# decoupling.net
KiCad netlist of a schematic drawn in Altium Designer
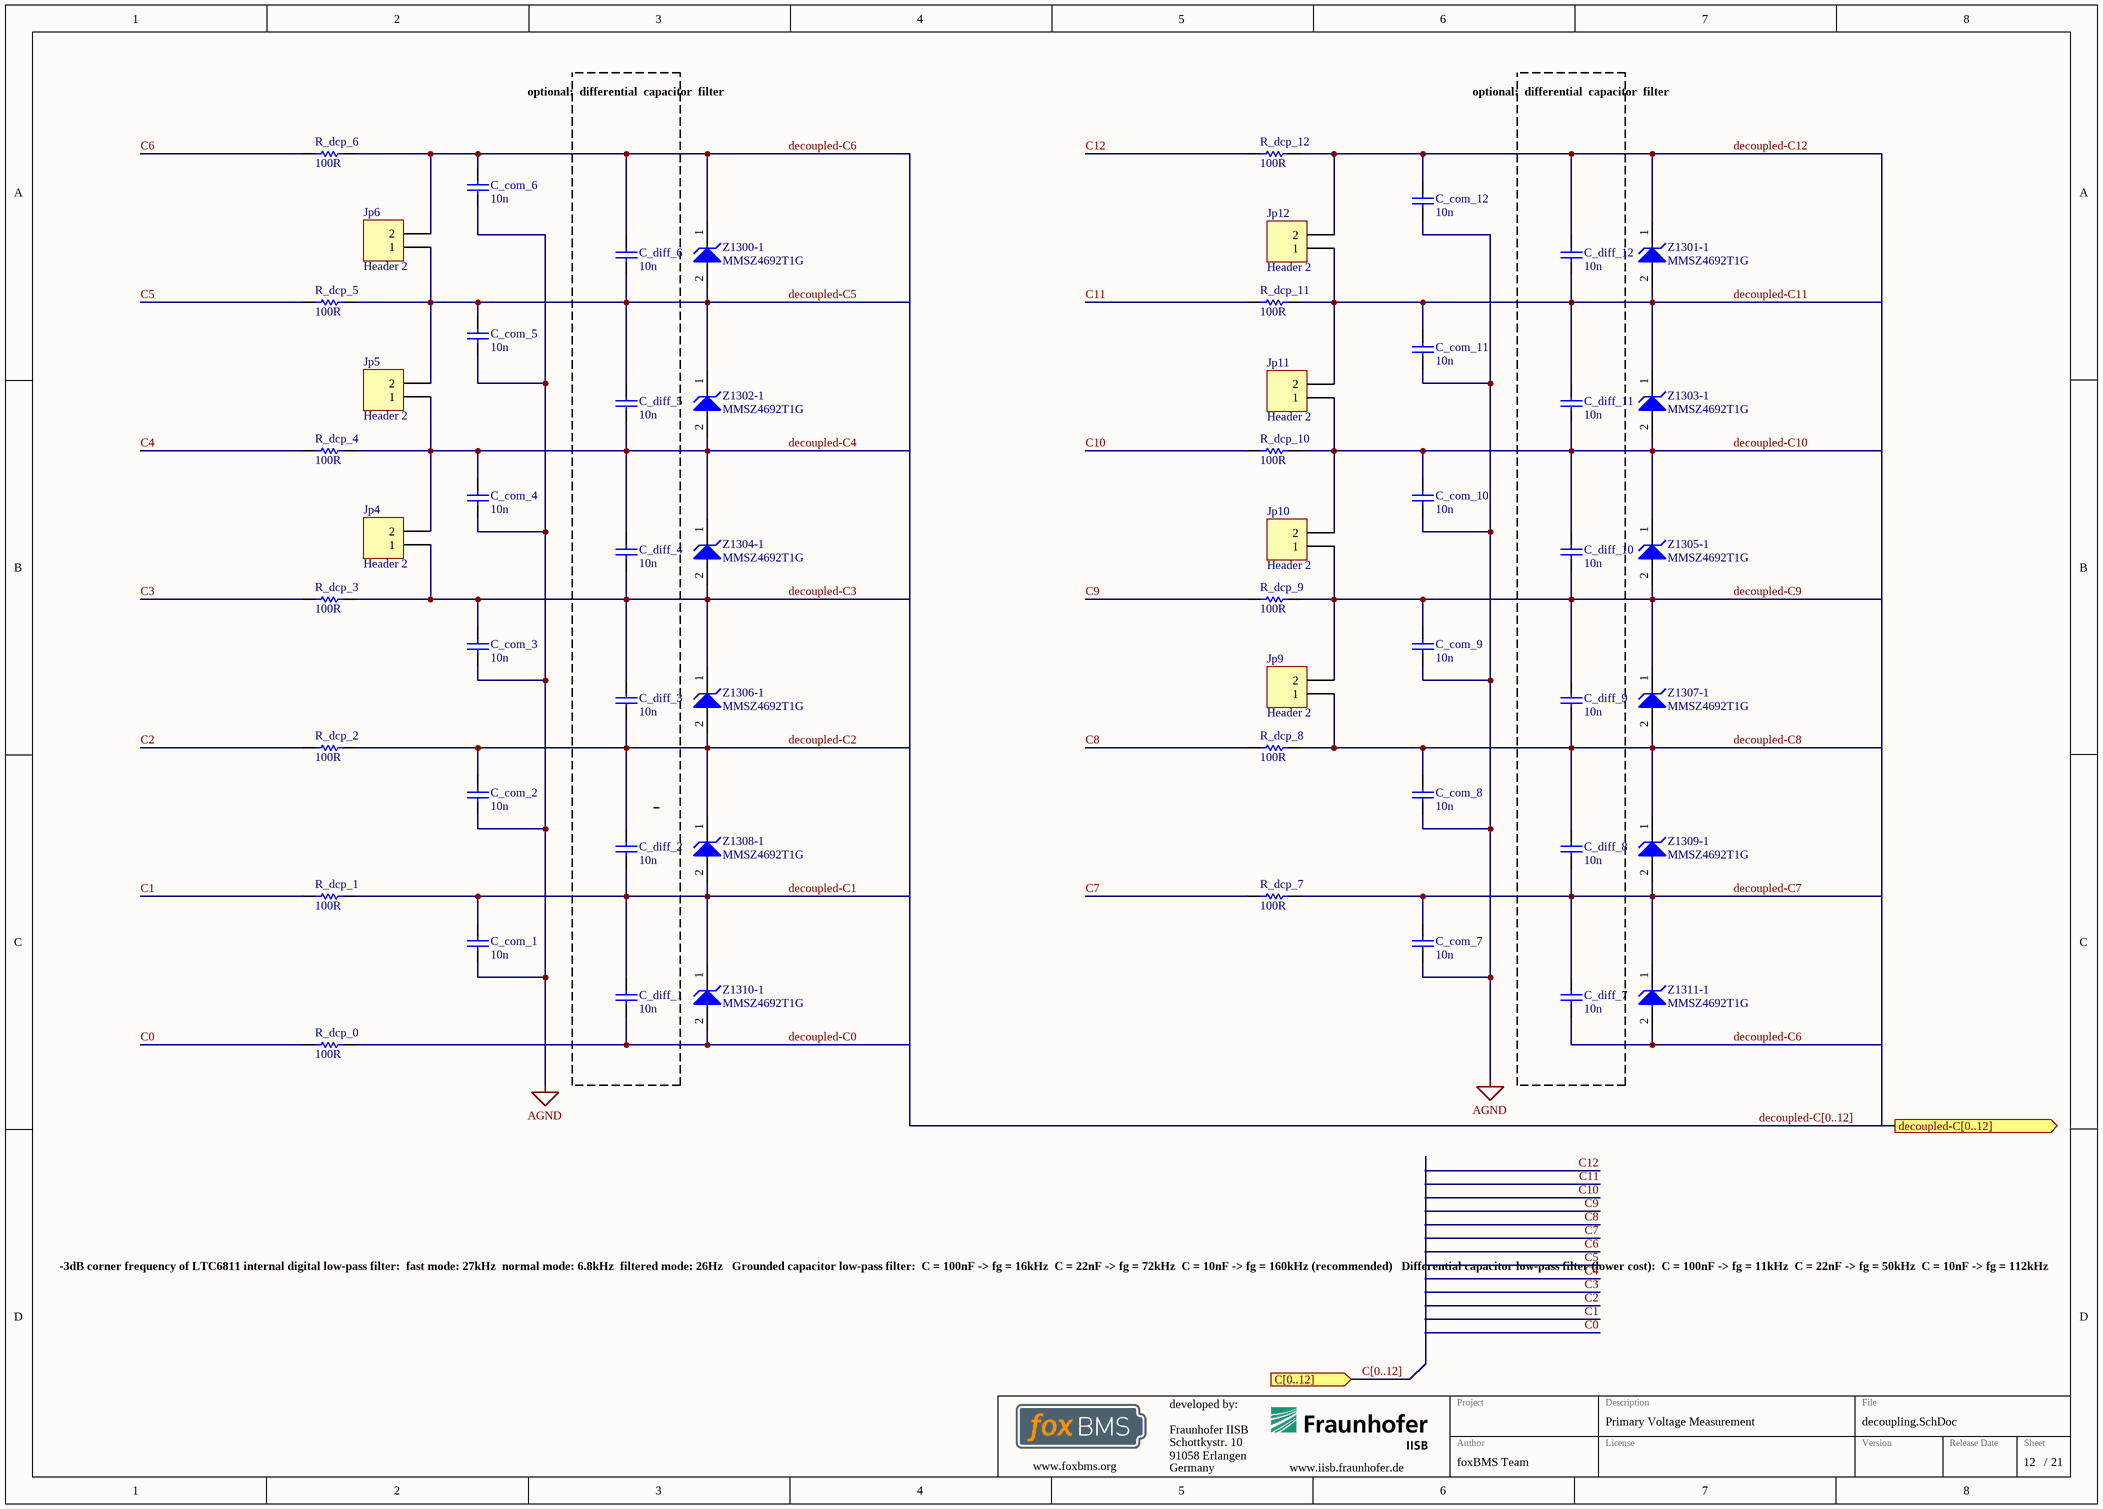
[diagram p0: decoupling.SchDoc]

(export (version "E")
  (design (tool "Eeschema 10.0.6"))
  (components
    (comp (ref "C_com_1")
      (value "10n")
      (footprint "CAPC0603(1608)55_N")
      (description "Keramikvielschichtkondensator, SMD, Baureihe MC, ± 10%")
      (fields (field (name "MANUFACTURER") "TDK") (field (name "TOLERANCE") "± 10%"))
      (libsource (lib "Res&Caps") (part "Cap 10n"))
    )
    (comp (ref "C_com_2")
      (value "10n")
      (footprint "CAPC0603(1608)55_N")
      (description "Keramikvielschichtkondensator, SMD, Baureihe MC, ± 10%")
      (fields (field (name "MANUFACTURER") "TDK") (field (name "TOLERANCE") "± 10%"))
      (libsource (lib "Res&Caps") (part "Cap 10n"))
    )
    (comp (ref "C_com_3")
      (value "10n")
      (footprint "CAPC0603(1608)55_N")
      (description "Keramikvielschichtkondensator, SMD, Baureihe MC, ± 10%")
      (fields (field (name "MANUFACTURER") "TDK") (field (name "TOLERANCE") "± 10%"))
      (libsource (lib "Res&Caps") (part "Cap 10n"))
    )
    (comp (ref "C_com_4")
      (value "10n")
      (footprint "CAPC0603(1608)55_N")
      (description "Keramikvielschichtkondensator, SMD, Baureihe MC, ± 10%")
      (fields (field (name "MANUFACTURER") "TDK") (field (name "TOLERANCE") "± 10%"))
      (libsource (lib "Res&Caps") (part "Cap 10n"))
    )
    (comp (ref "C_com_5")
      (value "10n")
      (footprint "CAPC0603(1608)55_N")
      (description "Keramikvielschichtkondensator, SMD, Baureihe MC, ± 10%")
      (fields (field (name "MANUFACTURER") "TDK") (field (name "TOLERANCE") "± 10%"))
      (libsource (lib "Res&Caps") (part "Cap 10n"))
    )
    (comp (ref "C_com_6")
      (value "10n")
      (footprint "CAPC0603(1608)55_N")
      (description "Keramikvielschichtkondensator, SMD, Baureihe MC, ± 10%")
      (fields (field (name "MANUFACTURER") "TDK") (field (name "TOLERANCE") "± 10%"))
      (libsource (lib "Res&Caps") (part "Cap 10n"))
    )
    (comp (ref "C_com_7")
      (value "10n")
      (footprint "CAPC0603(1608)55_N")
      (description "Keramikvielschichtkondensator, SMD, Baureihe MC, ± 10%")
      (fields (field (name "MANUFACTURER") "TDK") (field (name "TOLERANCE") "± 10%"))
      (libsource (lib "Res&Caps") (part "Cap 10n"))
    )
    (comp (ref "C_com_8")
      (value "10n")
      (footprint "CAPC0603(1608)55_N")
      (description "Keramikvielschichtkondensator, SMD, Baureihe MC, ± 10%")
      (fields (field (name "MANUFACTURER") "TDK") (field (name "TOLERANCE") "± 10%"))
      (libsource (lib "Res&Caps") (part "Cap 10n"))
    )
    (comp (ref "C_com_9")
      (value "10n")
      (footprint "CAPC0603(1608)55_N")
      (description "Keramikvielschichtkondensator, SMD, Baureihe MC, ± 10%")
      (fields (field (name "MANUFACTURER") "TDK") (field (name "TOLERANCE") "± 10%"))
      (libsource (lib "Res&Caps") (part "Cap 10n"))
    )
    (comp (ref "C_com_10")
      (value "10n")
      (footprint "CAPC0603(1608)55_N")
      (description "Keramikvielschichtkondensator, SMD, Baureihe MC, ± 10%")
      (fields (field (name "MANUFACTURER") "TDK") (field (name "TOLERANCE") "± 10%"))
      (libsource (lib "Res&Caps") (part "Cap 10n"))
    )
    (comp (ref "C_com_11")
      (value "10n")
      (footprint "CAPC0603(1608)55_N")
      (description "Keramikvielschichtkondensator, SMD, Baureihe MC, ± 10%")
      (fields (field (name "MANUFACTURER") "TDK") (field (name "TOLERANCE") "± 10%"))
      (libsource (lib "Res&Caps") (part "Cap 10n"))
    )
    (comp (ref "C_com_12")
      (value "10n")
      (footprint "CAPC0603(1608)55_N")
      (description "Keramikvielschichtkondensator, SMD, Baureihe MC, ± 10%")
      (fields (field (name "MANUFACTURER") "TDK") (field (name "TOLERANCE") "± 10%"))
      (libsource (lib "Res&Caps") (part "Cap 10n"))
    )
    (comp (ref "C_diff_1")
      (value "10n")
      (footprint "CAPC0603(1608)55_N")
      (description "Keramikvielschichtkondensator, SMD, Baureihe MC, ± 10%")
      (fields (field (name "MANUFACTURER") "TDK") (field (name "TOLERANCE") "± 10%"))
      (libsource (lib "Res&Caps") (part "Cap 10n"))
    )
    (comp (ref "C_diff_2")
      (value "10n")
      (footprint "CAPC0603(1608)55_N")
      (description "Keramikvielschichtkondensator, SMD, Baureihe MC, ± 10%")
      (fields (field (name "MANUFACTURER") "TDK") (field (name "TOLERANCE") "± 10%"))
      (libsource (lib "Res&Caps") (part "Cap 10n"))
    )
    (comp (ref "C_diff_3")
      (value "10n")
      (footprint "CAPC0603(1608)55_N")
      (description "Keramikvielschichtkondensator, SMD, Baureihe MC, ± 10%")
      (fields (field (name "MANUFACTURER") "TDK") (field (name "TOLERANCE") "± 10%"))
      (libsource (lib "Res&Caps") (part "Cap 10n"))
    )
    (comp (ref "C_diff_4")
      (value "10n")
      (footprint "CAPC0603(1608)55_N")
      (description "Keramikvielschichtkondensator, SMD, Baureihe MC, ± 10%")
      (fields (field (name "MANUFACTURER") "TDK") (field (name "TOLERANCE") "± 10%"))
      (libsource (lib "Res&Caps") (part "Cap 10n"))
    )
    (comp (ref "C_diff_5")
      (value "10n")
      (footprint "CAPC0603(1608)55_N")
      (description "Keramikvielschichtkondensator, SMD, Baureihe MC, ± 10%")
      (fields (field (name "MANUFACTURER") "TDK") (field (name "TOLERANCE") "± 10%"))
      (libsource (lib "Res&Caps") (part "Cap 10n"))
    )
    (comp (ref "C_diff_6")
      (value "10n")
      (footprint "CAPC0603(1608)55_N")
      (description "Keramikvielschichtkondensator, SMD, Baureihe MC, ± 10%")
      (fields (field (name "MANUFACTURER") "TDK") (field (name "TOLERANCE") "± 10%"))
      (libsource (lib "Res&Caps") (part "Cap 10n"))
    )
    (comp (ref "C_diff_7")
      (value "10n")
      (footprint "CAPC0603(1608)55_N")
      (description "Keramikvielschichtkondensator, SMD, Baureihe MC, ± 10%")
      (fields (field (name "MANUFACTURER") "TDK") (field (name "TOLERANCE") "± 10%"))
      (libsource (lib "Res&Caps") (part "Cap 10n"))
    )
    (comp (ref "C_diff_8")
      (value "10n")
      (footprint "CAPC0603(1608)55_N")
      (description "Keramikvielschichtkondensator, SMD, Baureihe MC, ± 10%")
      (fields (field (name "MANUFACTURER") "TDK") (field (name "TOLERANCE") "± 10%"))
      (libsource (lib "Res&Caps") (part "Cap 10n"))
    )
    (comp (ref "C_diff_9")
      (value "10n")
      (footprint "CAPC0603(1608)55_N")
      (description "Keramikvielschichtkondensator, SMD, Baureihe MC, ± 10%")
      (fields (field (name "MANUFACTURER") "TDK") (field (name "TOLERANCE") "± 10%"))
      (libsource (lib "Res&Caps") (part "Cap 10n"))
    )
    (comp (ref "C_diff_10")
      (value "10n")
      (footprint "CAPC0603(1608)55_N")
      (description "Keramikvielschichtkondensator, SMD, Baureihe MC, ± 10%")
      (fields (field (name "MANUFACTURER") "TDK") (field (name "TOLERANCE") "± 10%"))
      (libsource (lib "Res&Caps") (part "Cap 10n"))
    )
    (comp (ref "C_diff_11")
      (value "10n")
      (footprint "CAPC0603(1608)55_N")
      (description "Keramikvielschichtkondensator, SMD, Baureihe MC, ± 10%")
      (fields (field (name "MANUFACTURER") "TDK") (field (name "TOLERANCE") "± 10%"))
      (libsource (lib "Res&Caps") (part "Cap 10n"))
    )
    (comp (ref "C_diff_12")
      (value "10n")
      (footprint "CAPC0603(1608)55_N")
      (description "Keramikvielschichtkondensator, SMD, Baureihe MC, ± 10%")
      (fields (field (name "MANUFACTURER") "TDK") (field (name "TOLERANCE") "± 10%"))
      (libsource (lib "Res&Caps") (part "Cap 10n"))
    )
    (comp (ref "Jp4")
      (value "Header 2")
      (footprint "HDR1X2")
      (description "Header, 2-Pin")
      (fields (field (name "PUBLISHER") "Altium Limited"))
      (libsource (lib "Miscellaneous Connectors") (part "Header 2"))
    )
    (comp (ref "Jp5")
      (value "Header 2")
      (footprint "HDR1X2")
      (description "Header, 2-Pin")
      (fields (field (name "PUBLISHER") "Altium Limited"))
      (libsource (lib "Miscellaneous Connectors") (part "Header 2"))
    )
    (comp (ref "Jp6")
      (value "Header 2")
      (footprint "HDR1X2")
      (description "Header, 2-Pin")
      (fields (field (name "PUBLISHER") "Altium Limited"))
      (libsource (lib "Miscellaneous Connectors") (part "Header 2"))
    )
    (comp (ref "Jp9")
      (value "Header 2")
      (footprint "HDR1X2")
      (description "Header, 2-Pin")
      (fields (field (name "PUBLISHER") "Altium Limited"))
      (libsource (lib "Miscellaneous Connectors") (part "Header 2"))
    )
    (comp (ref "Jp10")
      (value "Header 2")
      (footprint "HDR1X2")
      (description "Header, 2-Pin")
      (fields (field (name "PUBLISHER") "Altium Limited"))
      (libsource (lib "Miscellaneous Connectors") (part "Header 2"))
    )
    (comp (ref "Jp11")
      (value "Header 2")
      (footprint "HDR1X2")
      (description "Header, 2-Pin")
      (fields (field (name "PUBLISHER") "Altium Limited"))
      (libsource (lib "Miscellaneous Connectors") (part "Header 2"))
    )
    (comp (ref "Jp12")
      (value "Header 2")
      (footprint "HDR1X2")
      (description "Header, 2-Pin")
      (fields (field (name "PUBLISHER") "Altium Limited"))
      (libsource (lib "Miscellaneous Connectors") (part "Header 2"))
    )
    (comp (ref "R_dcp_0")
      (value "100R")
      (footprint "RESC0603(1608)_N")
      (description "Chipwiderstand, SMD, Baureihe MC, 1%")
      (fields (field (name "MANUFACTURER") "Multicomp") (field (name "POWER") "100mW"))
      (libsource (lib "Res&Caps") (part "Res 100R"))
    )
    (comp (ref "R_dcp_1")
      (value "100R")
      (footprint "RESC0603(1608)_N")
      (description "Chipwiderstand, SMD, Baureihe MC, 1%")
      (fields (field (name "MANUFACTURER") "Multicomp") (field (name "POWER") "100mW"))
      (libsource (lib "Res&Caps") (part "Res 100R"))
    )
    (comp (ref "R_dcp_2")
      (value "100R")
      (footprint "RESC0603(1608)_N")
      (description "Chipwiderstand, SMD, Baureihe MC, 1%")
      (fields (field (name "MANUFACTURER") "Multicomp") (field (name "POWER") "100mW"))
      (libsource (lib "Res&Caps") (part "Res 100R"))
    )
    (comp (ref "R_dcp_3")
      (value "100R")
      (footprint "RESC0603(1608)_N")
      (description "Chipwiderstand, SMD, Baureihe MC, 1%")
      (fields (field (name "MANUFACTURER") "Multicomp") (field (name "POWER") "100mW"))
      (libsource (lib "Res&Caps") (part "Res 100R"))
    )
    (comp (ref "R_dcp_4")
      (value "100R")
      (footprint "RESC0603(1608)_N")
      (description "Chipwiderstand, SMD, Baureihe MC, 1%")
      (fields (field (name "MANUFACTURER") "Multicomp") (field (name "POWER") "100mW"))
      (libsource (lib "Res&Caps") (part "Res 100R"))
    )
    (comp (ref "R_dcp_5")
      (value "100R")
      (footprint "RESC0603(1608)_N")
      (description "Chipwiderstand, SMD, Baureihe MC, 1%")
      (fields (field (name "MANUFACTURER") "Multicomp") (field (name "POWER") "100mW"))
      (libsource (lib "Res&Caps") (part "Res 100R"))
    )
    (comp (ref "R_dcp_6")
      (value "100R")
      (footprint "RESC0603(1608)_N")
      (description "Chipwiderstand, SMD, Baureihe MC, 1%")
      (fields (field (name "MANUFACTURER") "Multicomp") (field (name "POWER") "100mW"))
      (libsource (lib "Res&Caps") (part "Res 100R"))
    )
    (comp (ref "R_dcp_7")
      (value "100R")
      (footprint "RESC0603(1608)_N")
      (description "Chipwiderstand, SMD, Baureihe MC, 1%")
      (fields (field (name "MANUFACTURER") "Multicomp") (field (name "POWER") "100mW"))
      (libsource (lib "Res&Caps") (part "Res 100R"))
    )
    (comp (ref "R_dcp_8")
      (value "100R")
      (footprint "RESC0603(1608)_N")
      (description "Chipwiderstand, SMD, Baureihe MC, 1%")
      (fields (field (name "MANUFACTURER") "Multicomp") (field (name "POWER") "100mW"))
      (libsource (lib "Res&Caps") (part "Res 100R"))
    )
    (comp (ref "R_dcp_9")
      (value "100R")
      (footprint "RESC0603(1608)_N")
      (description "Chipwiderstand, SMD, Baureihe MC, 1%")
      (fields (field (name "MANUFACTURER") "Multicomp") (field (name "POWER") "100mW"))
      (libsource (lib "Res&Caps") (part "Res 100R"))
    )
    (comp (ref "R_dcp_10")
      (value "100R")
      (footprint "RESC0603(1608)_N")
      (description "Chipwiderstand, SMD, Baureihe MC, 1%")
      (fields (field (name "MANUFACTURER") "Multicomp") (field (name "POWER") "100mW"))
      (libsource (lib "Res&Caps") (part "Res 100R"))
    )
    (comp (ref "R_dcp_11")
      (value "100R")
      (footprint "RESC0603(1608)_N")
      (description "Chipwiderstand, SMD, Baureihe MC, 1%")
      (fields (field (name "MANUFACTURER") "Multicomp") (field (name "POWER") "100mW"))
      (libsource (lib "Res&Caps") (part "Res 100R"))
    )
    (comp (ref "R_dcp_12")
      (value "100R")
      (footprint "RESC0603(1608)_N")
      (description "Chipwiderstand, SMD, Baureihe MC, 1%")
      (fields (field (name "MANUFACTURER") "Multicomp") (field (name "POWER") "100mW"))
      (libsource (lib "Res&Caps") (part "Res 100R"))
    )
    (comp (ref "Z1300-1")
      (value "MMSZ4692T1G")
      (footprint "ONSC-SOD-123-2-425-04_V")
      (description "Zener Voltage Regulator, 500 mW, 2-Pin SOD-123, Pb-Free, Tape and Reel")
      (fields (field (name "MANUFACTURER") "On Semiconductor"))
      (libsource (lib "Altium Content Vault") (part "ONSC-K1A2-2"))
    )
    (comp (ref "Z1301-1")
      (value "MMSZ4692T1G")
      (footprint "ONSC-SOD-123-2-425-04_V")
      (description "Zener Voltage Regulator, 500 mW, 2-Pin SOD-123, Pb-Free, Tape and Reel")
      (fields (field (name "MANUFACTURER") "On Semiconductor"))
      (libsource (lib "Altium Content Vault") (part "ONSC-K1A2-2"))
    )
    (comp (ref "Z1302-1")
      (value "MMSZ4692T1G")
      (footprint "ONSC-SOD-123-2-425-04_V")
      (description "Zener Voltage Regulator, 500 mW, 2-Pin SOD-123, Pb-Free, Tape and Reel")
      (fields (field (name "MANUFACTURER") "On Semiconductor"))
      (libsource (lib "Altium Content Vault") (part "ONSC-K1A2-2"))
    )
    (comp (ref "Z1303-1")
      (value "MMSZ4692T1G")
      (footprint "ONSC-SOD-123-2-425-04_V")
      (description "Zener Voltage Regulator, 500 mW, 2-Pin SOD-123, Pb-Free, Tape and Reel")
      (fields (field (name "MANUFACTURER") "On Semiconductor"))
      (libsource (lib "Altium Content Vault") (part "ONSC-K1A2-2"))
    )
    (comp (ref "Z1304-1")
      (value "MMSZ4692T1G")
      (footprint "ONSC-SOD-123-2-425-04_V")
      (description "Zener Voltage Regulator, 500 mW, 2-Pin SOD-123, Pb-Free, Tape and Reel")
      (fields (field (name "MANUFACTURER") "On Semiconductor"))
      (libsource (lib "Altium Content Vault") (part "ONSC-K1A2-2"))
    )
    (comp (ref "Z1305-1")
      (value "MMSZ4692T1G")
      (footprint "ONSC-SOD-123-2-425-04_V")
      (description "Zener Voltage Regulator, 500 mW, 2-Pin SOD-123, Pb-Free, Tape and Reel")
      (fields (field (name "MANUFACTURER") "On Semiconductor"))
      (libsource (lib "Altium Content Vault") (part "ONSC-K1A2-2"))
    )
    (comp (ref "Z1306-1")
      (value "MMSZ4692T1G")
      (footprint "ONSC-SOD-123-2-425-04_V")
      (description "Zener Voltage Regulator, 500 mW, 2-Pin SOD-123, Pb-Free, Tape and Reel")
      (fields (field (name "MANUFACTURER") "On Semiconductor"))
      (libsource (lib "Altium Content Vault") (part "ONSC-K1A2-2"))
    )
    (comp (ref "Z1307-1")
      (value "MMSZ4692T1G")
      (footprint "ONSC-SOD-123-2-425-04_V")
      (description "Zener Voltage Regulator, 500 mW, 2-Pin SOD-123, Pb-Free, Tape and Reel")
      (fields (field (name "MANUFACTURER") "On Semiconductor"))
      (libsource (lib "Altium Content Vault") (part "ONSC-K1A2-2"))
    )
    (comp (ref "Z1308-1")
      (value "MMSZ4692T1G")
      (footprint "ONSC-SOD-123-2-425-04_V")
      (description "Zener Voltage Regulator, 500 mW, 2-Pin SOD-123, Pb-Free, Tape and Reel")
      (fields (field (name "MANUFACTURER") "On Semiconductor"))
      (libsource (lib "Altium Content Vault") (part "ONSC-K1A2-2"))
    )
    (comp (ref "Z1309-1")
      (value "MMSZ4692T1G")
      (footprint "ONSC-SOD-123-2-425-04_V")
      (description "Zener Voltage Regulator, 500 mW, 2-Pin SOD-123, Pb-Free, Tape and Reel")
      (fields (field (name "MANUFACTURER") "On Semiconductor"))
      (libsource (lib "Altium Content Vault") (part "ONSC-K1A2-2"))
    )
    (comp (ref "Z1310-1")
      (value "MMSZ4692T1G")
      (footprint "ONSC-SOD-123-2-425-04_V")
      (description "Zener Voltage Regulator, 500 mW, 2-Pin SOD-123, Pb-Free, Tape and Reel")
      (fields (field (name "MANUFACTURER") "On Semiconductor"))
      (libsource (lib "Altium Content Vault") (part "ONSC-K1A2-2"))
    )
    (comp (ref "Z1311-1")
      (value "MMSZ4692T1G")
      (footprint "ONSC-SOD-123-2-425-04_V")
      (description "Zener Voltage Regulator, 500 mW, 2-Pin SOD-123, Pb-Free, Tape and Reel")
      (fields (field (name "MANUFACTURER") "On Semiconductor"))
      (libsource (lib "Altium Content Vault") (part "ONSC-K1A2-2"))
    )
  )
  (nets
    (net (code "1") (name "/C0") (class "Default")
      (node (ref "R_dcp_0") (pin "1") (pinfunction "1_1") (pintype "passive"))
    )
    (net (code "2") (name "/C1") (class "Default")
      (node (ref "R_dcp_1") (pin "1") (pinfunction "1_1") (pintype "passive"))
    )
    (net (code "3") (name "/C2") (class "Default")
      (node (ref "R_dcp_2") (pin "1") (pinfunction "1_1") (pintype "passive"))
    )
    (net (code "4") (name "/C3") (class "Default")
      (node (ref "R_dcp_3") (pin "1") (pinfunction "1_1") (pintype "passive"))
    )
    (net (code "5") (name "/C4") (class "Default")
      (node (ref "R_dcp_4") (pin "1") (pinfunction "1_1") (pintype "passive"))
    )
    (net (code "6") (name "/C5") (class "Default")
      (node (ref "R_dcp_5") (pin "1") (pinfunction "1_1") (pintype "passive"))
    )
    (net (code "7") (name "/C6") (class "Default")
      (node (ref "R_dcp_6") (pin "1") (pinfunction "1_1") (pintype "passive"))
    )
    (net (code "8") (name "/C7") (class "Default")
      (node (ref "R_dcp_7") (pin "1") (pinfunction "1_1") (pintype "passive"))
    )
    (net (code "9") (name "/C8") (class "Default")
      (node (ref "R_dcp_8") (pin "1") (pinfunction "1_1") (pintype "passive"))
    )
    (net (code "10") (name "/C9") (class "Default")
      (node (ref "R_dcp_9") (pin "1") (pinfunction "1_1") (pintype "passive"))
    )
    (net (code "11") (name "/C10") (class "Default")
      (node (ref "R_dcp_10") (pin "1") (pinfunction "1_1") (pintype "passive"))
    )
    (net (code "12") (name "/C11") (class "Default")
      (node (ref "R_dcp_11") (pin "1") (pinfunction "1_1") (pintype "passive"))
    )
    (net (code "13") (name "/C12") (class "Default")
      (node (ref "R_dcp_12") (pin "1") (pinfunction "1_1") (pintype "passive"))
    )
    (net (code "15") (name "/decoupled-C0") (class "Default")
      (node (ref "C_diff_1") (pin "1") (pinfunction "1_1") (pintype "passive"))
      (node (ref "R_dcp_0") (pin "2") (pinfunction "2_2") (pintype "passive"))
      (node (ref "Z1310-1") (pin "2") (pinfunction "A_2") (pintype "passive"))
    )
    (net (code "16") (name "/decoupled-C1") (class "Default")
      (node (ref "C_com_1") (pin "2") (pinfunction "2_2") (pintype "passive"))
      (node (ref "C_diff_1") (pin "2") (pinfunction "2_2") (pintype "passive"))
      (node (ref "C_diff_2") (pin "1") (pinfunction "1_1") (pintype "passive"))
      (node (ref "R_dcp_1") (pin "2") (pinfunction "2_2") (pintype "passive"))
      (node (ref "Z1308-1") (pin "2") (pinfunction "A_2") (pintype "passive"))
      (node (ref "Z1310-1") (pin "1") (pinfunction "K_1") (pintype "passive"))
    )
    (net (code "17") (name "/decoupled-C2") (class "Default")
      (node (ref "C_com_2") (pin "2") (pinfunction "2_2") (pintype "passive"))
      (node (ref "C_diff_2") (pin "2") (pinfunction "2_2") (pintype "passive"))
      (node (ref "C_diff_3") (pin "1") (pinfunction "1_1") (pintype "passive"))
      (node (ref "R_dcp_2") (pin "2") (pinfunction "2_2") (pintype "passive"))
      (node (ref "Z1306-1") (pin "2") (pinfunction "A_2") (pintype "passive"))
      (node (ref "Z1308-1") (pin "1") (pinfunction "K_1") (pintype "passive"))
    )
    (net (code "18") (name "/decoupled-C3") (class "Default")
      (node (ref "C_com_3") (pin "2") (pinfunction "2_2") (pintype "passive"))
      (node (ref "C_diff_3") (pin "2") (pinfunction "2_2") (pintype "passive"))
      (node (ref "C_diff_4") (pin "1") (pinfunction "1_1") (pintype "passive"))
      (node (ref "Jp4") (pin "1") (pinfunction "1_1") (pintype "passive"))
      (node (ref "R_dcp_3") (pin "2") (pinfunction "2_2") (pintype "passive"))
      (node (ref "Z1304-1") (pin "2") (pinfunction "A_2") (pintype "passive"))
      (node (ref "Z1306-1") (pin "1") (pinfunction "K_1") (pintype "passive"))
    )
    (net (code "19") (name "/decoupled-C4") (class "Default")
      (node (ref "C_com_4") (pin "2") (pinfunction "2_2") (pintype "passive"))
      (node (ref "C_diff_4") (pin "2") (pinfunction "2_2") (pintype "passive"))
      (node (ref "C_diff_5") (pin "1") (pinfunction "1_1") (pintype "passive"))
      (node (ref "Jp4") (pin "2") (pinfunction "2_2") (pintype "passive"))
      (node (ref "Jp5") (pin "1") (pinfunction "1_1") (pintype "passive"))
      (node (ref "R_dcp_4") (pin "2") (pinfunction "2_2") (pintype "passive"))
      (node (ref "Z1302-1") (pin "2") (pinfunction "A_2") (pintype "passive"))
      (node (ref "Z1304-1") (pin "1") (pinfunction "K_1") (pintype "passive"))
    )
    (net (code "20") (name "/decoupled-C5") (class "Default")
      (node (ref "C_com_5") (pin "1") (pinfunction "1_1") (pintype "passive"))
      (node (ref "C_diff_5") (pin "2") (pinfunction "2_2") (pintype "passive"))
      (node (ref "C_diff_6") (pin "1") (pinfunction "1_1") (pintype "passive"))
      (node (ref "Jp5") (pin "2") (pinfunction "2_2") (pintype "passive"))
      (node (ref "Jp6") (pin "1") (pinfunction "1_1") (pintype "passive"))
      (node (ref "R_dcp_5") (pin "2") (pinfunction "2_2") (pintype "passive"))
      (node (ref "Z1300-1") (pin "2") (pinfunction "A_2") (pintype "passive"))
      (node (ref "Z1302-1") (pin "1") (pinfunction "K_1") (pintype "passive"))
    )
    (net (code "21") (name "/decoupled-C6") (class "Default")
      (node (ref "C_com_6") (pin "1") (pinfunction "1_1") (pintype "passive"))
      (node (ref "C_diff_6") (pin "2") (pinfunction "2_2") (pintype "passive"))
      (node (ref "C_diff_7") (pin "1") (pinfunction "1_1") (pintype "passive"))
      (node (ref "Jp6") (pin "2") (pinfunction "2_2") (pintype "passive"))
      (node (ref "R_dcp_6") (pin "2") (pinfunction "2_2") (pintype "passive"))
      (node (ref "Z1300-1") (pin "1") (pinfunction "K_1") (pintype "passive"))
      (node (ref "Z1311-1") (pin "2") (pinfunction "A_2") (pintype "passive"))
    )
    (net (code "22") (name "/decoupled-C7") (class "Default")
      (node (ref "C_com_7") (pin "2") (pinfunction "2_2") (pintype "passive"))
      (node (ref "C_diff_7") (pin "2") (pinfunction "2_2") (pintype "passive"))
      (node (ref "C_diff_8") (pin "1") (pinfunction "1_1") (pintype "passive"))
      (node (ref "R_dcp_7") (pin "2") (pinfunction "2_2") (pintype "passive"))
      (node (ref "Z1309-1") (pin "2") (pinfunction "A_2") (pintype "passive"))
      (node (ref "Z1311-1") (pin "1") (pinfunction "K_1") (pintype "passive"))
    )
    (net (code "23") (name "/decoupled-C8") (class "Default")
      (node (ref "C_com_8") (pin "2") (pinfunction "2_2") (pintype "passive"))
      (node (ref "C_diff_8") (pin "2") (pinfunction "2_2") (pintype "passive"))
      (node (ref "C_diff_9") (pin "1") (pinfunction "1_1") (pintype "passive"))
      (node (ref "Jp9") (pin "1") (pinfunction "1_1") (pintype "passive"))
      (node (ref "R_dcp_8") (pin "2") (pinfunction "2_2") (pintype "passive"))
      (node (ref "Z1307-1") (pin "2") (pinfunction "A_2") (pintype "passive"))
      (node (ref "Z1309-1") (pin "1") (pinfunction "K_1") (pintype "passive"))
    )
    (net (code "24") (name "/decoupled-C9") (class "Default")
      (node (ref "C_com_9") (pin "2") (pinfunction "2_2") (pintype "passive"))
      (node (ref "C_diff_10") (pin "1") (pinfunction "1_1") (pintype "passive"))
      (node (ref "C_diff_9") (pin "2") (pinfunction "2_2") (pintype "passive"))
      (node (ref "Jp10") (pin "1") (pinfunction "1_1") (pintype "passive"))
      (node (ref "Jp9") (pin "2") (pinfunction "2_2") (pintype "passive"))
      (node (ref "R_dcp_9") (pin "2") (pinfunction "2_2") (pintype "passive"))
      (node (ref "Z1305-1") (pin "2") (pinfunction "A_2") (pintype "passive"))
      (node (ref "Z1307-1") (pin "1") (pinfunction "K_1") (pintype "passive"))
    )
    (net (code "25") (name "/decoupled-C10") (class "Default")
      (node (ref "C_com_10") (pin "2") (pinfunction "2_2") (pintype "passive"))
      (node (ref "C_diff_10") (pin "2") (pinfunction "2_2") (pintype "passive"))
      (node (ref "C_diff_11") (pin "1") (pinfunction "1_1") (pintype "passive"))
      (node (ref "Jp10") (pin "2") (pinfunction "2_2") (pintype "passive"))
      (node (ref "Jp11") (pin "1") (pinfunction "1_1") (pintype "passive"))
      (node (ref "R_dcp_10") (pin "2") (pinfunction "2_2") (pintype "passive"))
      (node (ref "Z1303-1") (pin "2") (pinfunction "A_2") (pintype "passive"))
      (node (ref "Z1305-1") (pin "1") (pinfunction "K_1") (pintype "passive"))
    )
    (net (code "26") (name "/decoupled-C11") (class "Default")
      (node (ref "C_com_11") (pin "2") (pinfunction "2_2") (pintype "passive"))
      (node (ref "C_diff_11") (pin "2") (pinfunction "2_2") (pintype "passive"))
      (node (ref "C_diff_12") (pin "1") (pinfunction "1_1") (pintype "passive"))
      (node (ref "Jp11") (pin "2") (pinfunction "2_2") (pintype "passive"))
      (node (ref "Jp12") (pin "1") (pinfunction "1_1") (pintype "passive"))
      (node (ref "R_dcp_11") (pin "2") (pinfunction "2_2") (pintype "passive"))
      (node (ref "Z1301-1") (pin "2") (pinfunction "A_2") (pintype "passive"))
      (node (ref "Z1303-1") (pin "1") (pinfunction "K_1") (pintype "passive"))
    )
    (net (code "27") (name "/decoupled-C12") (class "Default")
      (node (ref "C_com_12") (pin "2") (pinfunction "2_2") (pintype "passive"))
      (node (ref "C_diff_12") (pin "2") (pinfunction "2_2") (pintype "passive"))
      (node (ref "Jp12") (pin "2") (pinfunction "2_2") (pintype "passive"))
      (node (ref "R_dcp_12") (pin "2") (pinfunction "2_2") (pintype "passive"))
      (node (ref "Z1301-1") (pin "1") (pinfunction "K_1") (pintype "passive"))
    )
    (net (code "29") (name "AGND") (class "Default")
      (node (ref "C_com_1") (pin "1") (pinfunction "1_1") (pintype "passive"))
      (node (ref "C_com_10") (pin "1") (pinfunction "1_1") (pintype "passive"))
      (node (ref "C_com_11") (pin "1") (pinfunction "1_1") (pintype "passive"))
      (node (ref "C_com_12") (pin "1") (pinfunction "1_1") (pintype "passive"))
      (node (ref "C_com_2") (pin "1") (pinfunction "1_1") (pintype "passive"))
      (node (ref "C_com_3") (pin "1") (pinfunction "1_1") (pintype "passive"))
      (node (ref "C_com_4") (pin "1") (pinfunction "1_1") (pintype "passive"))
      (node (ref "C_com_5") (pin "2") (pinfunction "2_2") (pintype "passive"))
      (node (ref "C_com_6") (pin "2") (pinfunction "2_2") (pintype "passive"))
      (node (ref "C_com_7") (pin "1") (pinfunction "1_1") (pintype "passive"))
      (node (ref "C_com_8") (pin "1") (pinfunction "1_1") (pintype "passive"))
      (node (ref "C_com_9") (pin "1") (pinfunction "1_1") (pintype "passive"))
    )
  )
)
